# bGeigieNanoKit.net
KiCad netlist of a schematic drawn in EAGLE
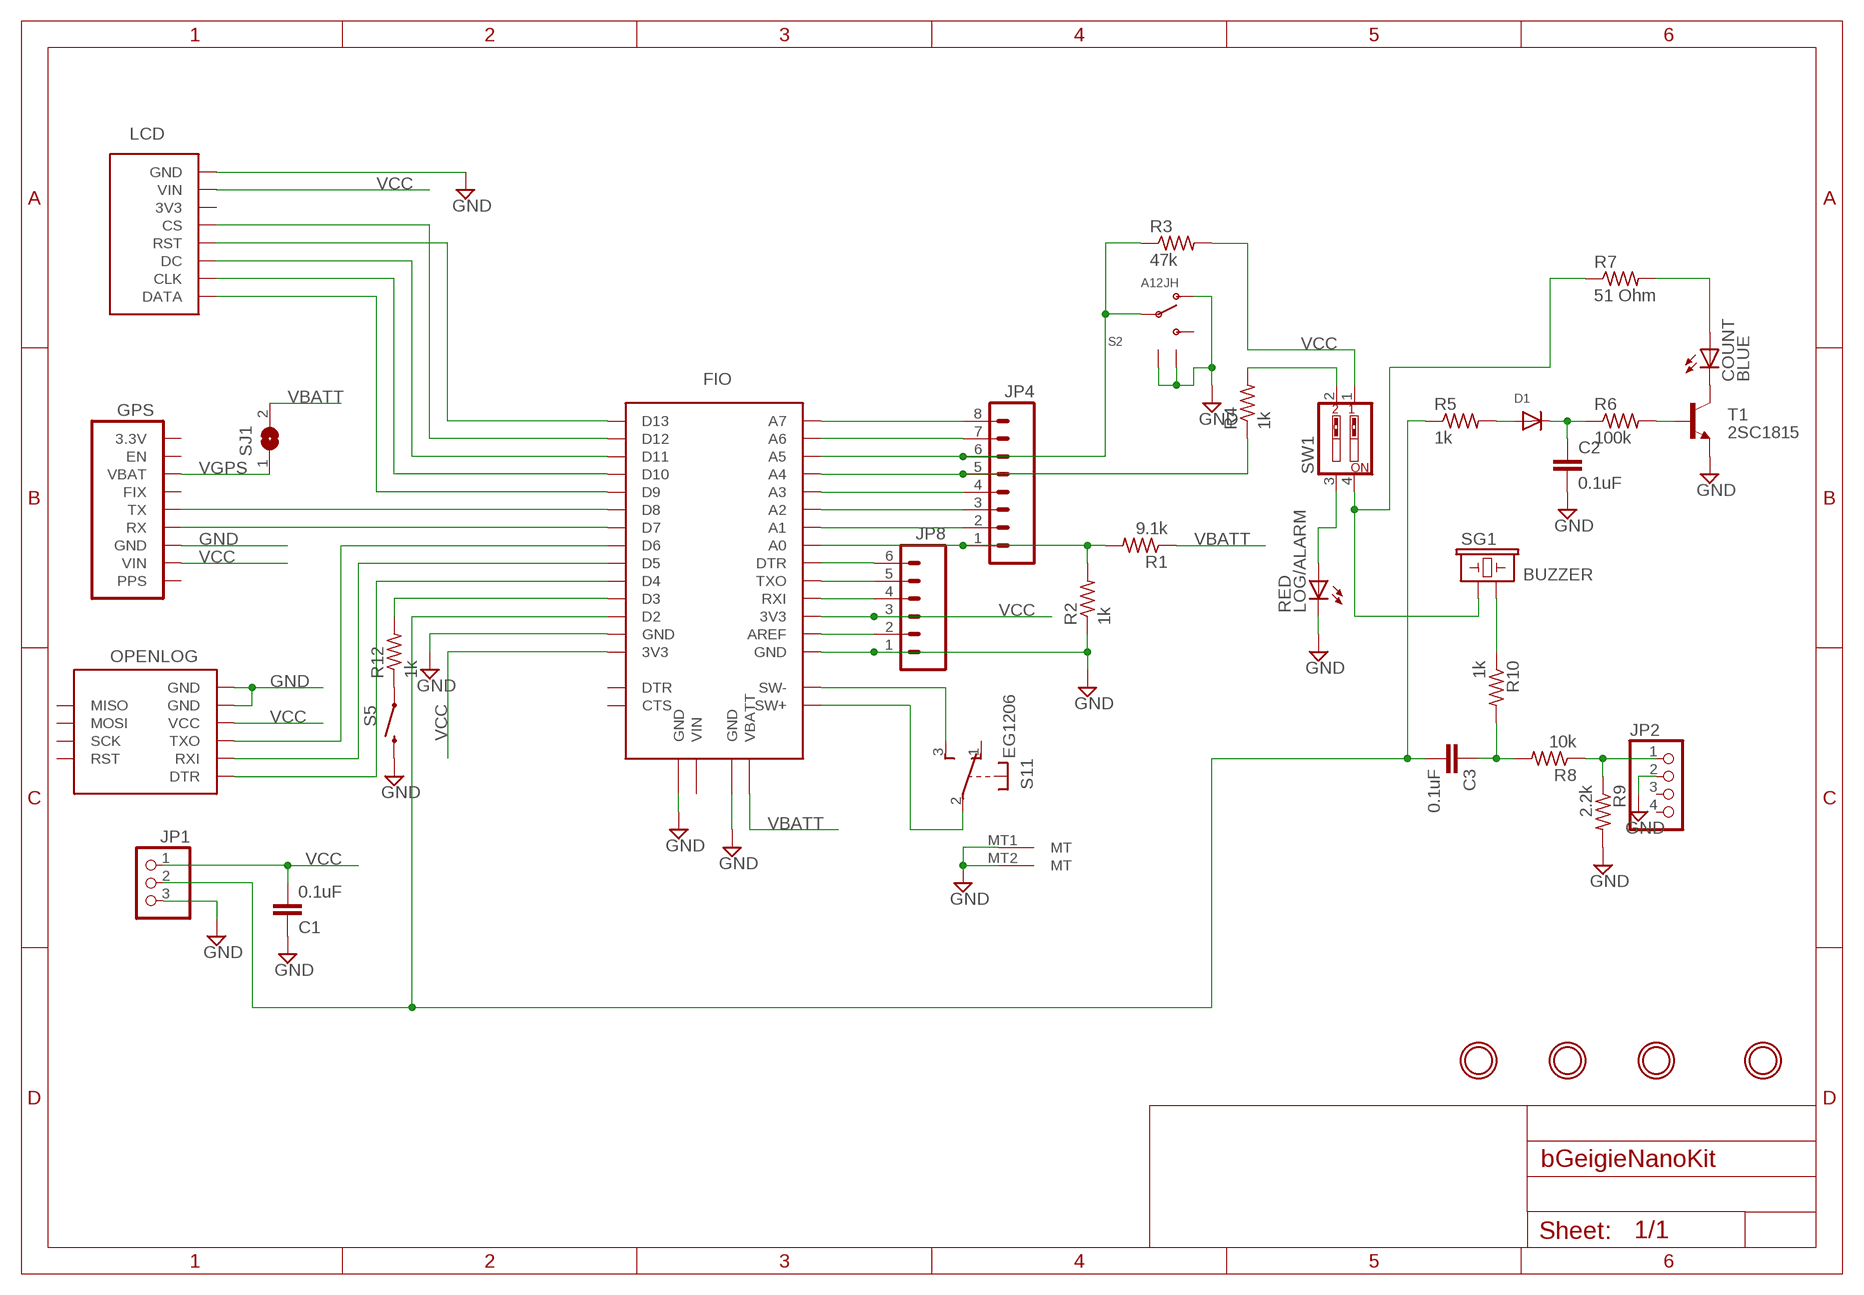
[diagram p0: schematic, sheet 1]

(export (version "E")
  (design (tool "Eeschema 10.0.6"))
  (components
    (comp (ref "C1")
      (value "0.1uF")
      (footprint "eagle-import:C025-024X044")
      (libsource (lib "eagle-import") (part "C-EU025-024X044"))
    )
    (comp (ref "C2")
      (value "0.1uF")
      (footprint "eagle-import:C025-024X044")
      (libsource (lib "eagle-import") (part "C-EU025-024X044"))
    )
    (comp (ref "C3")
      (value "0.1uF")
      (footprint "eagle-import:C025-024X044")
      (libsource (lib "eagle-import") (part "C-EU025-024X044"))
    )
    (comp (ref "COUNT")
      (value "BLUE")
      (footprint "eagle-import:LED3MM")
      (libsource (lib "eagle-import") (part "LED3MM"))
    )
    (comp (ref "D1")
      (value "DIODEDO-1N4148")
      (footprint "eagle-import:DO-1N4148")
      (libsource (lib "eagle-import") (part "DIODEDO-1N4148"))
    )
    (comp (ref "FIO")
      (value "FIO_SOCKETBOT")
      (footprint "eagle-import:FIO_V23_SOCKET_BOT")
      (libsource (lib "eagle-import") (part "FIO_SOCKETBOT"))
    )
    (comp (ref "GPS")
      (value "ULTIMATE_GPSTOP")
      (footprint "eagle-import:ULTIMATE_GPS_V3_TOP")
      (libsource (lib "eagle-import") (part "ULTIMATE_GPSTOP"))
    )
    (comp (ref "JP1")
      (value "PINHD-1X3/90")
      (footprint "eagle-import:1X03_90")
      (libsource (lib "eagle-import") (part "PINHD-1X3/90"))
    )
    (comp (ref "JP2")
      (value "HEADER-1X4ROUND")
      (footprint "eagle-import:1X04_ROUND")
      (libsource (lib "eagle-import") (part "HEADER-1X4ROUND"))
    )
    (comp (ref "JP4")
      (value "M081X08")
      (footprint "eagle-import:1X08")
      (libsource (lib "eagle-import") (part "M081X08"))
    )
    (comp (ref "JP8")
      (value "M06SIP")
      (footprint "eagle-import:1X06")
      (libsource (lib "eagle-import") (part "M06SIP"))
    )
    (comp (ref "LCD")
      (value "SSD1306_128X64_V2_LCD1.3IN_LEVER")
      (footprint "eagle-import:SSD1306_128X64_1.3IN_LCD_LEVER")
      (libsource (lib "eagle-import") (part "SSD1306_128X64_V2_LCD1.3IN_LEVER"))
    )
    (comp (ref "LOG/ALARM")
      (value "RED")
      (footprint "eagle-import:LED3MM")
      (libsource (lib "eagle-import") (part "LED3MM"))
    )
    (comp (ref "OPENLOG")
      (value "OPENLOG")
      (footprint "eagle-import:OPENLOG")
      (libsource (lib "eagle-import") (part "OPENLOG"))
    )
    (comp (ref "R1")
      (value "9.1k")
      (footprint "eagle-import:0207_10")
      (libsource (lib "eagle-import") (part "R-US_0207/10"))
    )
    (comp (ref "R2")
      (value "1k")
      (footprint "eagle-import:0207_10")
      (libsource (lib "eagle-import") (part "R-US_0207/10"))
    )
    (comp (ref "R3")
      (value "47k")
      (footprint "eagle-import:0207_10")
      (libsource (lib "eagle-import") (part "R-US_0207/10"))
    )
    (comp (ref "R4")
      (value "1k")
      (footprint "eagle-import:0207_10")
      (libsource (lib "eagle-import") (part "R-US_0207/10"))
    )
    (comp (ref "R5")
      (value "1k")
      (footprint "eagle-import:0207_10")
      (libsource (lib "eagle-import") (part "R-US_0207/10"))
    )
    (comp (ref "R6")
      (value "100k")
      (footprint "eagle-import:0207_10")
      (libsource (lib "eagle-import") (part "R-US_0207/10"))
    )
    (comp (ref "R7")
      (value "51 Ohm")
      (footprint "eagle-import:0207_10")
      (libsource (lib "eagle-import") (part "R-US_0207/10"))
    )
    (comp (ref "R8")
      (value "10k")
      (footprint "eagle-import:0207_10")
      (libsource (lib "eagle-import") (part "R-US_0207/10"))
    )
    (comp (ref "R9")
      (value "2.2k")
      (footprint "eagle-import:0207_10")
      (libsource (lib "eagle-import") (part "R-US_0207/10"))
    )
    (comp (ref "R10")
      (value "1k")
      (footprint "eagle-import:0207_10")
      (libsource (lib "eagle-import") (part "R-US_0207/10"))
    )
    (comp (ref "R12")
      (value "1k")
      (footprint "eagle-import:0207_10")
      (libsource (lib "eagle-import") (part "R-US_0207/10"))
    )
    (comp (ref "S1")
      (value "EG1206")
      (footprint "eagle-import:EG1206")
      (libsource (lib "eagle-import") (part "EG1206"))
    )
    (comp (ref "S2")
      (value "A12JH")
      (footprint "eagle-import:A12AH")
      (libsource (lib "eagle-import") (part "A12JH"))
    )
    (comp (ref "S5")
      (value "SWITCH-MOMENTARY-2PTH")
      (footprint "eagle-import:TACTILE-PTH")
      (libsource (lib "eagle-import") (part "SWITCH-MOMENTARY-2PTH"))
    )
    (comp (ref "SG1")
      (value "BUZZER")
      (footprint "eagle-import:BUZZER-12MM")
      (libsource (lib "eagle-import") (part "BUZZERPTH"))
    )
    (comp (ref "SJ1")
      (value "SOLDERJUMPERCLOSED")
      (footprint "eagle-import:SOLDERJUMPER_CLOSEDWIRE")
      (libsource (lib "eagle-import") (part "SOLDERJUMPERCLOSED"))
    )
    (comp (ref "SW1")
      (value "SW_DIP-2")
      (footprint "eagle-import:EDG-02")
      (libsource (lib "eagle-import") (part "SW_DIP-2"))
    )
    (comp (ref "T1")
      (value "2SC1815")
      (footprint "eagle-import:TO92-ECB")
      (libsource (lib "eagle-import") (part "2SC1815"))
    )
    (comp (ref "U$6")
      (value "MOUNTINGHOLE3.0THIN")
      (footprint "eagle-import:MOUNTINGHOLE_3.0_PLATEDTHIN")
      (libsource (lib "eagle-import") (part "MOUNTINGHOLE3.0THIN"))
    )
    (comp (ref "U$7")
      (value "MOUNTINGHOLE3.0THIN")
      (footprint "eagle-import:MOUNTINGHOLE_3.0_PLATEDTHIN")
      (libsource (lib "eagle-import") (part "MOUNTINGHOLE3.0THIN"))
    )
    (comp (ref "U$8")
      (value "MOUNTINGHOLE3.0THIN")
      (footprint "eagle-import:MOUNTINGHOLE_3.0_PLATEDTHIN")
      (libsource (lib "eagle-import") (part "MOUNTINGHOLE3.0THIN"))
    )
    (comp (ref "U$9")
      (value "MOUNTINGHOLE3.0THIN")
      (footprint "eagle-import:MOUNTINGHOLE_3.0_PLATEDTHIN")
      (libsource (lib "eagle-import") (part "MOUNTINGHOLE3.0THIN"))
    )
  )
  (nets
    (net (code "1") (name "/3.3V") (class "Default")
      (node (ref "GPS") (pin "JP1$9") (pinfunction "3.3V_JP1$9") (pintype "power_in"))
    )
    (net (code "2") (name "/VBATT") (class "Default")
      (node (ref "FIO") (pin "JP2$2") (pinfunction "VBATT_JP2$2") (pintype "bidirectional"))
      (node (ref "R1") (pin "1") (pinfunction "1_1") (pintype "passive"))
      (node (ref "SJ1") (pin "2") (pinfunction "2_2") (pintype "passive"))
    )
    (net (code "3") (name "/VCC") (class "Default")
      (node (ref "C1") (pin "2") (pinfunction "2_2") (pintype "passive"))
      (node (ref "FIO") (pin "JP1$1") (pinfunction "3V3_JP1$1") (pintype "power_in"))
      (node (ref "FIO") (pin "JP5$3") (pinfunction "3V3_JP5$3") (pintype "power_in"))
      (node (ref "GPS") (pin "JP1$2") (pinfunction "VIN_JP1$2") (pintype "power_in"))
      (node (ref "JP1") (pin "1") (pinfunction "1_1") (pintype "passive"))
      (node (ref "JP8") (pin "3") (pinfunction "3_3") (pintype "passive"))
      (node (ref "LCD") (pin "JP1$7") (pinfunction "VIN_JP1$7") (pintype "power_in"))
      (node (ref "OPENLOG") (pin "JP1$4") (pinfunction "VCC_JP1$4") (pintype "power_in"))
      (node (ref "R3") (pin "2") (pinfunction "2_2") (pintype "passive"))
      (node (ref "SW1") (pin "1") (pinfunction "1_1") (pintype "passive"))
    )
    (net (code "4") (name "/VGPS") (class "Default")
      (node (ref "GPS") (pin "JP1$7") (pinfunction "VBAT_JP1$7") (pintype "power_in"))
      (node (ref "SJ1") (pin "1") (pinfunction "1_1") (pintype "passive"))
    )
    (net (code "5") (name "GND") (class "Default")
      (node (ref "C1") (pin "1") (pinfunction "1_1") (pintype "passive"))
      (node (ref "C2") (pin "2") (pinfunction "2_2") (pintype "passive"))
      (node (ref "FIO") (pin "JP1$2") (pinfunction "GND_JP1$2") (pintype "power_in"))
      (node (ref "FIO") (pin "JP2$1") (pinfunction "GND_JP2$1") (pintype "bidirectional"))
      (node (ref "FIO") (pin "JP5$1") (pinfunction "GND_JP5$1") (pintype "power_in"))
      (node (ref "FIO") (pin "JP6$1") (pinfunction "GND_JP6$1") (pintype "bidirectional"))
      (node (ref "GPS") (pin "JP1$3") (pinfunction "GND_JP1$3") (pintype "power_in"))
      (node (ref "GPS") (pin "U$8$P$1") (pinfunction "GND_U$8$P$1") (pintype "power_in"))
      (node (ref "GPS") (pin "U$9$P$1") (pinfunction "GND_U$9$P$1") (pintype "power_in"))
      (node (ref "JP1") (pin "3") (pinfunction "3_3") (pintype "passive"))
      (node (ref "JP2") (pin "2") (pinfunction "2_2") (pintype "passive"))
      (node (ref "JP8") (pin "1") (pinfunction "1_1") (pintype "passive"))
      (node (ref "LCD") (pin "JP1$8") (pinfunction "GND_JP1$8") (pintype "power_in"))
      (node (ref "LCD") (pin "U$23$P$1") (pinfunction "GND_U$23$P$1") (pintype "power_in"))
      (node (ref "LCD") (pin "U$26$P$1") (pinfunction "GND_U$26$P$1") (pintype "power_in"))
      (node (ref "LOG/ALARM") (pin "K") (pinfunction "C_K") (pintype "passive"))
      (node (ref "OPENLOG") (pin "JP1$5") (pinfunction "GND_JP1$5") (pintype "power_in"))
      (node (ref "OPENLOG") (pin "JP1$6") (pinfunction "GND_JP1$6") (pintype "power_in"))
      (node (ref "R2") (pin "1") (pinfunction "1_1") (pintype "passive"))
      (node (ref "R9") (pin "2") (pinfunction "2_2") (pintype "passive"))
      (node (ref "S1") (pin "MT1") (pinfunction "MT_MT1") (pintype "passive"))
      (node (ref "S1") (pin "MT2") (pinfunction "MT_MT2") (pintype "passive"))
      (node (ref "S2") (pin "P$1") (pinfunction "P$1_P$1") (pintype "passive"))
      (node (ref "S2") (pin "P$4") (pinfunction "GND_P$4") (pintype "power_in"))
      (node (ref "S2") (pin "P$5") (pinfunction "GND_P$5") (pintype "power_in"))
      (node (ref "S5") (pin "3") (pinfunction "2_3") (pintype "passive"))
      (node (ref "T1") (pin "E") (pinfunction "E_E") (pintype "passive"))
    )
    (net (code "6") (name "Net-(C2-Pad1)") (class "Default")
      (node (ref "C2") (pin "1") (pinfunction "1_1") (pintype "passive"))
      (node (ref "D1") (pin "C") (pinfunction "C_C") (pintype "passive"))
      (node (ref "R6") (pin "1") (pinfunction "1_1") (pintype "passive"))
    )
    (net (code "7") (name "Net-(C3-Pad1)") (class "Default")
      (node (ref "C3") (pin "1") (pinfunction "1_1") (pintype "passive"))
      (node (ref "R10") (pin "2") (pinfunction "2_2") (pintype "passive"))
      (node (ref "R8") (pin "2") (pinfunction "2_2") (pintype "passive"))
    )
    (net (code "8") (name "Net-(COUNT-C)") (class "Default")
      (node (ref "COUNT") (pin "K") (pinfunction "C_K") (pintype "passive"))
      (node (ref "T1") (pin "C") (pinfunction "C_C") (pintype "passive"))
    )
    (net (code "9") (name "Net-(COUNT-PadA)") (class "Default")
      (node (ref "COUNT") (pin "A") (pinfunction "A_A") (pintype "passive"))
      (node (ref "R7") (pin "2") (pinfunction "2_2") (pintype "passive"))
    )
    (net (code "10") (name "Net-(D1-PadA)") (class "Default")
      (node (ref "D1") (pin "A") (pinfunction "A_A") (pintype "passive"))
      (node (ref "R5") (pin "2") (pinfunction "2_2") (pintype "passive"))
    )
    (net (code "11") (name "Net-(FIO-A0)") (class "Default")
      (node (ref "FIO") (pin "JP5$7") (pinfunction "A0_JP5$7") (pintype "bidirectional"))
      (node (ref "JP4") (pin "1") (pinfunction "1_1") (pintype "passive"))
      (node (ref "R1") (pin "2") (pinfunction "2_2") (pintype "passive"))
      (node (ref "R2") (pin "2") (pinfunction "2_2") (pintype "passive"))
    )
    (net (code "12") (name "Net-(FIO-A1)") (class "Default")
      (node (ref "FIO") (pin "JP5$8") (pinfunction "A1_JP5$8") (pintype "bidirectional"))
      (node (ref "JP4") (pin "2") (pinfunction "2_2") (pintype "passive"))
    )
    (net (code "13") (name "Net-(FIO-A2)") (class "Default")
      (node (ref "FIO") (pin "JP5$9") (pinfunction "A2_JP5$9") (pintype "bidirectional"))
      (node (ref "JP4") (pin "3") (pinfunction "3_3") (pintype "passive"))
    )
    (net (code "14") (name "Net-(FIO-A3)") (class "Default")
      (node (ref "FIO") (pin "JP5$10") (pinfunction "A3_JP5$10") (pintype "bidirectional"))
      (node (ref "JP4") (pin "4") (pinfunction "4_4") (pintype "passive"))
    )
    (net (code "15") (name "Net-(FIO-A4)") (class "Default")
      (node (ref "FIO") (pin "JP5$11") (pinfunction "A4_JP5$11") (pintype "bidirectional"))
      (node (ref "JP4") (pin "5") (pinfunction "5_5") (pintype "passive"))
      (node (ref "R4") (pin "1") (pinfunction "1_1") (pintype "passive"))
    )
    (net (code "16") (name "Net-(FIO-A5)") (class "Default")
      (node (ref "FIO") (pin "JP5$12") (pinfunction "A5_JP5$12") (pintype "bidirectional"))
      (node (ref "JP4") (pin "6") (pinfunction "6_6") (pintype "passive"))
      (node (ref "R3") (pin "1") (pinfunction "1_1") (pintype "passive"))
      (node (ref "S2") (pin "P$2") (pinfunction "P$2_P$2") (pintype "passive"))
    )
    (net (code "17") (name "Net-(FIO-A6)") (class "Default")
      (node (ref "FIO") (pin "JP5$13") (pinfunction "A6_JP5$13") (pintype "bidirectional"))
      (node (ref "JP4") (pin "7") (pinfunction "7_7") (pintype "passive"))
    )
    (net (code "18") (name "Net-(FIO-A7)") (class "Default")
      (node (ref "FIO") (pin "JP5$14") (pinfunction "A7_JP5$14") (pintype "bidirectional"))
      (node (ref "JP4") (pin "8") (pinfunction "8_8") (pintype "passive"))
    )
    (net (code "19") (name "Net-(FIO-AREF)") (class "Default")
      (node (ref "FIO") (pin "JP5$2") (pinfunction "AREF_JP5$2") (pintype "output"))
      (node (ref "JP8") (pin "2") (pinfunction "2_2") (pintype "passive"))
    )
    (net (code "20") (name "Net-(FIO-D2)") (class "Default")
      (node (ref "C3") (pin "2") (pinfunction "2_2") (pintype "passive"))
      (node (ref "FIO") (pin "JP1$3") (pinfunction "D2_JP1$3") (pintype "bidirectional"))
      (node (ref "JP1") (pin "2") (pinfunction "2_2") (pintype "passive"))
      (node (ref "R5") (pin "1") (pinfunction "1_1") (pintype "passive"))
    )
    (net (code "21") (name "Net-(FIO-D3)") (class "Default")
      (node (ref "FIO") (pin "JP1$4") (pinfunction "D3_JP1$4") (pintype "bidirectional"))
      (node (ref "R12") (pin "2") (pinfunction "2_2") (pintype "passive"))
    )
    (net (code "22") (name "Net-(FIO-D4)") (class "Default")
      (node (ref "FIO") (pin "JP1$5") (pinfunction "D4_JP1$5") (pintype "bidirectional"))
      (node (ref "OPENLOG") (pin "JP1$1") (pinfunction "DTR_JP1$1") (pintype "input"))
    )
    (net (code "23") (name "Net-(FIO-D5)") (class "Default")
      (node (ref "FIO") (pin "JP1$6") (pinfunction "D5_JP1$6") (pintype "bidirectional"))
      (node (ref "OPENLOG") (pin "JP1$2") (pinfunction "RXI_JP1$2") (pintype "input"))
    )
    (net (code "24") (name "Net-(FIO-D6)") (class "Default")
      (node (ref "FIO") (pin "JP1$7") (pinfunction "D6_JP1$7") (pintype "bidirectional"))
      (node (ref "OPENLOG") (pin "JP1$3") (pinfunction "TXO_JP1$3") (pintype "output"))
    )
    (net (code "25") (name "Net-(FIO-D7)") (class "Default")
      (node (ref "FIO") (pin "JP1$8") (pinfunction "D7_JP1$8") (pintype "bidirectional"))
      (node (ref "GPS") (pin "JP1$4") (pinfunction "RX_JP1$4") (pintype "input"))
    )
    (net (code "26") (name "Net-(FIO-D8)") (class "Default")
      (node (ref "FIO") (pin "JP1$9") (pinfunction "D8_JP1$9") (pintype "bidirectional"))
      (node (ref "GPS") (pin "JP1$5") (pinfunction "TX_JP1$5") (pintype "output"))
    )
    (net (code "27") (name "Net-(FIO-D9)") (class "Default")
      (node (ref "FIO") (pin "JP1$10") (pinfunction "D9_JP1$10") (pintype "bidirectional"))
      (node (ref "LCD") (pin "JP1$1") (pinfunction "DATA_JP1$1") (pintype "bidirectional"))
    )
    (net (code "28") (name "Net-(FIO-D10)") (class "Default")
      (node (ref "FIO") (pin "JP1$11") (pinfunction "D10_JP1$11") (pintype "bidirectional"))
      (node (ref "LCD") (pin "JP1$2") (pinfunction "CLK_JP1$2") (pintype "bidirectional"))
    )
    (net (code "29") (name "Net-(FIO-D11)") (class "Default")
      (node (ref "FIO") (pin "JP1$12") (pinfunction "D11_JP1$12") (pintype "bidirectional"))
      (node (ref "LCD") (pin "JP1$3") (pinfunction "DC_JP1$3") (pintype "bidirectional"))
    )
    (net (code "30") (name "Net-(FIO-D12)") (class "Default")
      (node (ref "FIO") (pin "JP1$13") (pinfunction "D12_JP1$13") (pintype "bidirectional"))
      (node (ref "LCD") (pin "JP1$5") (pinfunction "CS_JP1$5") (pintype "bidirectional"))
    )
    (net (code "31") (name "Net-(FIO-D13)") (class "Default")
      (node (ref "FIO") (pin "JP1$14") (pinfunction "D13_JP1$14") (pintype "bidirectional"))
      (node (ref "LCD") (pin "JP1$4") (pinfunction "RST_JP1$4") (pintype "bidirectional"))
    )
    (net (code "32") (name "Net-(FIO-DTR-PadJP5$6)") (class "Default")
      (node (ref "FIO") (pin "JP5$6") (pinfunction "DTR_JP5$6") (pintype "input"))
      (node (ref "JP8") (pin "6") (pinfunction "6_6") (pintype "passive"))
    )
    (net (code "33") (name "Net-(FIO-RXI)") (class "Default")
      (node (ref "FIO") (pin "JP5$4") (pinfunction "RXI_JP5$4") (pintype "input"))
      (node (ref "JP8") (pin "4") (pinfunction "4_4") (pintype "passive"))
    )
    (net (code "34") (name "Net-(FIO-SW+)") (class "Default")
      (node (ref "FIO") (pin "JP7$2") (pinfunction "SW+_JP7$2") (pintype "bidirectional"))
      (node (ref "S1") (pin "2") (pinfunction "P_2") (pintype "passive"))
    )
    (net (code "35") (name "Net-(FIO-SW-)") (class "Default")
      (node (ref "FIO") (pin "JP7$1") (pinfunction "SW-_JP7$1") (pintype "bidirectional"))
      (node (ref "S1") (pin "3") (pinfunction "S_3") (pintype "passive"))
    )
    (net (code "36") (name "Net-(FIO-TXO)") (class "Default")
      (node (ref "FIO") (pin "JP5$5") (pinfunction "TXO_JP5$5") (pintype "output"))
      (node (ref "JP8") (pin "5") (pinfunction "5_5") (pintype "passive"))
    )
    (net (code "37") (name "Net-(JP2-Pad1)") (class "Default")
      (node (ref "JP2") (pin "1") (pinfunction "1_1") (pintype "passive"))
      (node (ref "R8") (pin "1") (pinfunction "1_1") (pintype "passive"))
      (node (ref "R9") (pin "1") (pinfunction "1_1") (pintype "passive"))
    )
    (net (code "38") (name "Net-(LOG/ALARM-PadA)") (class "Default")
      (node (ref "LOG/ALARM") (pin "A") (pinfunction "A_A") (pintype "passive"))
      (node (ref "SW1") (pin "3") (pinfunction "3_3") (pintype "passive"))
    )
    (net (code "39") (name "Net-(R4-Pad2)") (class "Default")
      (node (ref "R4") (pin "2") (pinfunction "2_2") (pintype "passive"))
      (node (ref "SW1") (pin "2") (pinfunction "2_2") (pintype "passive"))
    )
    (net (code "40") (name "Net-(R6-Pad2)") (class "Default")
      (node (ref "R6") (pin "2") (pinfunction "2_2") (pintype "passive"))
      (node (ref "T1") (pin "B") (pinfunction "B_B") (pintype "passive"))
    )
    (net (code "41") (name "Net-(R12-Pad1)") (class "Default")
      (node (ref "R12") (pin "1") (pinfunction "1_1") (pintype "passive"))
      (node (ref "S5") (pin "1") (pinfunction "1_1") (pintype "passive"))
    )
    (net (code "42") (name "Net-(SG1-1)") (class "Default")
      (node (ref "R7") (pin "1") (pinfunction "1_1") (pintype "passive"))
      (node (ref "SG1") (pin "+") (pinfunction "1_+") (pintype "passive"))
      (node (ref "SW1") (pin "4") (pinfunction "4_4") (pintype "passive"))
    )
    (net (code "43") (name "Net-(SG1-2)") (class "Default")
      (node (ref "R10") (pin "1") (pinfunction "1_1") (pintype "passive"))
      (node (ref "SG1") (pin "-") (pinfunction "2_-") (pintype "passive"))
    )
    (net (code "44") (name "unconnected-(FIO-CTS-PadJP8$1)") (class "Default")
      (node (ref "FIO") (pin "JP8$1") (pinfunction "CTS_JP8$1") (pintype "bidirectional"))
    )
    (net (code "45") (name "unconnected-(FIO-DTR-PadJP9$1)") (class "Default")
      (node (ref "FIO") (pin "JP9$1") (pinfunction "DTR_JP9$1") (pintype "bidirectional"))
    )
    (net (code "46") (name "unconnected-(FIO-VIN-PadJP6$2)") (class "Default")
      (node (ref "FIO") (pin "JP6$2") (pinfunction "VIN_JP6$2") (pintype "bidirectional"))
    )
    (net (code "47") (name "unconnected-(GPS-EN-PadJP1$8)") (class "Default")
      (node (ref "GPS") (pin "JP1$8") (pinfunction "EN_JP1$8") (pintype "input"))
    )
    (net (code "48") (name "unconnected-(GPS-FIX-PadJP1$6)") (class "Default")
      (node (ref "GPS") (pin "JP1$6") (pinfunction "FIX_JP1$6") (pintype "output"))
    )
    (net (code "49") (name "unconnected-(GPS-PPS-PadJP1$1)") (class "Default")
      (node (ref "GPS") (pin "JP1$1") (pinfunction "PPS_JP1$1") (pintype "output"))
    )
    (net (code "50") (name "unconnected-(JP2-Pad3)") (class "Default")
      (node (ref "JP2") (pin "3") (pinfunction "3_3") (pintype "passive"))
    )
    (net (code "51") (name "unconnected-(JP2-Pad4)") (class "Default")
      (node (ref "JP2") (pin "4") (pinfunction "4_4") (pintype "passive"))
    )
    (net (code "52") (name "unconnected-(LCD-3V3-PadJP1$6)") (class "Default")
      (node (ref "LCD") (pin "JP1$6") (pinfunction "3V3_JP1$6") (pintype "bidirectional"))
    )
    (net (code "53") (name "unconnected-(OPENLOG-MISO-PadJP2$4)") (class "Default")
      (node (ref "OPENLOG") (pin "JP2$4") (pinfunction "MISO_JP2$4") (pintype "bidirectional"))
    )
    (net (code "54") (name "unconnected-(OPENLOG-MOSI-PadJP2$3)") (class "Default")
      (node (ref "OPENLOG") (pin "JP2$3") (pinfunction "MOSI_JP2$3") (pintype "bidirectional"))
    )
    (net (code "55") (name "unconnected-(OPENLOG-RST-PadJP2$1)") (class "Default")
      (node (ref "OPENLOG") (pin "JP2$1") (pinfunction "RST_JP2$1") (pintype "input"))
    )
    (net (code "56") (name "unconnected-(OPENLOG-SCK-PadJP2$2)") (class "Default")
      (node (ref "OPENLOG") (pin "JP2$2") (pinfunction "SCK_JP2$2") (pintype "bidirectional"))
    )
    (net (code "57") (name "unconnected-(S1A-O-Pad1)") (class "Default")
      (node (ref "S1") (pin "1") (pinfunction "O_1") (pintype "passive"))
    )
    (net (code "58") (name "unconnected-(S2-PadP$3)") (class "Default")
      (node (ref "S2") (pin "P$3") (pinfunction "P$3_P$3") (pintype "passive"))
    )
  )
)
